# Ampli_ancha.net
KiCad netlist of a schematic drawn in Altium Designer
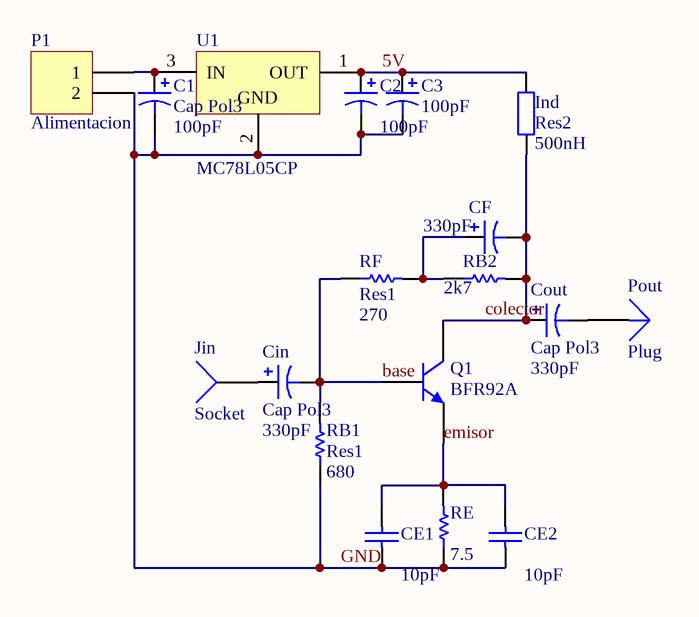
[diagram p0: Ampli_ancha.SchDoc]

(export (version "E")
  (design (tool "Eeschema 10.0.6"))
  (components
    (comp (ref "C1")
      (value "Cap Pol3")
      (footprint "C0805")
      (description "Polarized Capacitor (Surface Mount)")
      (fields (field (name "ALTIUM_VALUE") "100pF") (field (name "PUBLISHER") "Altium Limited"))
      (libsource (lib "Miscellaneous Devices") (part "Cap Pol3"))
    )
    (comp (ref "C2")
      (value "100pF")
      (footprint "C0805")
      (description "Polarized Capacitor (Surface Mount)")
      (fields (field (name "Comment") "Cap Pol3") (field (name "PUBLISHER") "Altium Limited"))
      (libsource (lib "Miscellaneous Devices") (part "Cap Pol3"))
    )
    (comp (ref "C3")
      (value "100pF")
      (footprint "C0805")
      (description "Polarized Capacitor (Surface Mount)")
      (fields (field (name "Comment") "Cap Pol3") (field (name "PUBLISHER") "Altium Limited"))
      (libsource (lib "Miscellaneous Devices") (part "Cap Pol3"))
    )
    (comp (ref "CE1")
      (value "10pF")
      (footprint "1608[0603]")
      (description "Capacitor (Semiconductor SIM Model)")
      (fields (field (name "Comment") "Cap Semi") (field (name "PUBLISHER") "Altium Limited"))
      (libsource (lib "Miscellaneous Devices") (part "Cap Semi"))
    )
    (comp (ref "CE2")
      (value "10pF")
      (footprint "1608[0603]")
      (description "Capacitor (Semiconductor SIM Model)")
      (fields (field (name "Comment") "Cap Semi") (field (name "PUBLISHER") "Altium Limited"))
      (libsource (lib "Miscellaneous Devices") (part "Cap Semi"))
    )
    (comp (ref "CF")
      (value "330pF")
      (footprint "C0805")
      (description "Polarized Capacitor (Surface Mount)")
      (fields (field (name "Comment") "Cap Pol3") (field (name "PUBLISHER") "Altium Limited"))
      (libsource (lib "Miscellaneous Devices") (part "Cap Pol3"))
    )
    (comp (ref "Cin")
      (value "Cap Pol3")
      (footprint "C0805")
      (description "Polarized Capacitor (Surface Mount)")
      (fields (field (name "ALTIUM_VALUE") "330pF") (field (name "PUBLISHER") "Altium Limited"))
      (libsource (lib "Miscellaneous Devices") (part "Cap Pol3"))
    )
    (comp (ref "Cout")
      (value "Cap Pol3")
      (footprint "C0805")
      (description "Polarized Capacitor (Surface Mount)")
      (fields (field (name "ALTIUM_VALUE") "330pF") (field (name "PUBLISHER") "Altium Limited"))
      (libsource (lib "Miscellaneous Devices") (part "Cap Pol3"))
    )
    (comp (ref "Ind")
      (value "Res2")
      (footprint "AXIAL-0.4")
      (description "Resistor")
      (fields (field (name "ALTIUM_VALUE") "500nH") (field (name "PUBLISHER") "Altium Limited"))
      (libsource (lib "Miscellaneous Devices") (part "Res2"))
    )
    (comp (ref "Jin")
      (value "Socket")
      (footprint "PIN1")
      (fields (field (name "PUBLISHER") "Altium Limited"))
      (libsource (lib "Miscellaneous Connectors") (part "Socket"))
    )
    (comp (ref "P1")
      (value "Alimentacion")
      (footprint "HDR1X2")
      (description "Header, 2-Pin")
      (fields (field (name "PUBLISHER") "Altium Limited"))
      (libsource (lib "Miscellaneous Connectors") (part "Header 2"))
    )
    (comp (ref "Pout")
      (value "Plug")
      (footprint "PIN1")
      (fields (field (name "PUBLISHER") "Altium Limited"))
      (libsource (lib "Miscellaneous Connectors") (part "Plug"))
    )
    (comp (ref "Q1")
      (value "BFR92A")
      (footprint "SOT23")
      (description "NPN 5 GHz Wideband Transistor")
      (fields (field (name "PUBLISHER") "Altium Limited"))
      (libsource (lib "Philips Discrete BJT - RF Transistor") (part "BFR92A"))
    )
    (comp (ref "RB1")
      (value "Res1")
      (footprint "AXIAL-0.3")
      (description "Resistor")
      (fields (field (name "ALTIUM_VALUE") "680") (field (name "PUBLISHER") "Altium Limited"))
      (libsource (lib "Miscellaneous Devices") (part "Res1"))
    )
    (comp (ref "RB2")
      (value "2k7")
      (footprint "AXIAL-0.3")
      (description "Resistor")
      (fields (field (name "Comment") "Res1") (field (name "PUBLISHER") "Altium Limited"))
      (libsource (lib "Miscellaneous Devices") (part "Res1"))
    )
    (comp (ref "RE")
      (value "7.5")
      (footprint "2012[0805]")
      (description "Semiconductor Resistor")
      (fields (field (name "Comment") "Res Semi") (field (name "PUBLISHER") "Altium Limited"))
      (libsource (lib "Miscellaneous Devices") (part "Res Semi"))
    )
    (comp (ref "RF")
      (value "Res1")
      (footprint "AXIAL-0.3")
      (description "Resistor")
      (fields (field (name "ALTIUM_VALUE") "270") (field (name "PUBLISHER") "Altium Limited"))
      (libsource (lib "Miscellaneous Devices") (part "Res1"))
    )
    (comp (ref "U1")
      (value "MC78L05CP")
      (footprint "29-04")
      (description "3-Terminal Low-Current Positive Fixed Voltage Regulator")
      (fields (field (name "PUBLISHER") "Altium Limited"))
      (libsource (lib "Motorola Power Mgt Voltage Regulator") (part "MC78L05CP"))
    )
  )
  (nets
    (net (code "1") (name "/5V") (class "Default")
      (node (ref "C2") (pin "1") (pinfunction "1_1") (pintype "passive"))
      (node (ref "C3") (pin "1") (pinfunction "1_1") (pintype "passive"))
      (node (ref "Ind") (pin "2") (pinfunction "2_2") (pintype "passive"))
      (node (ref "U1") (pin "1") (pinfunction "OUT_1") (pintype "power_in"))
    )
    (net (code "2") (name "/GND") (class "Default")
      (node (ref "C1") (pin "2") (pinfunction "2_2") (pintype "passive"))
      (node (ref "C2") (pin "2") (pinfunction "2_2") (pintype "passive"))
      (node (ref "C3") (pin "2") (pinfunction "2_2") (pintype "passive"))
      (node (ref "CE1") (pin "1") (pinfunction "1_1") (pintype "passive"))
      (node (ref "CE2") (pin "1") (pinfunction "1_1") (pintype "passive"))
      (node (ref "P1") (pin "2") (pinfunction "2_2") (pintype "passive"))
      (node (ref "RB1") (pin "1") (pinfunction "1_1") (pintype "passive"))
      (node (ref "RE") (pin "1") (pinfunction "1_1") (pintype "passive"))
      (node (ref "U1") (pin "2") (pinfunction "GND_2") (pintype "power_in"))
    )
    (net (code "3") (name "/base") (class "Default")
      (node (ref "Cin") (pin "2") (pinfunction "2_2") (pintype "passive"))
      (node (ref "Q1") (pin "1") (pinfunction "B_1") (pintype "passive"))
      (node (ref "RB1") (pin "2") (pinfunction "2_2") (pintype "passive"))
      (node (ref "RF") (pin "1") (pinfunction "1_1") (pintype "passive"))
    )
    (net (code "4") (name "/colector") (class "Default")
      (node (ref "CF") (pin "2") (pinfunction "2_2") (pintype "passive"))
      (node (ref "Cout") (pin "1") (pinfunction "1_1") (pintype "passive"))
      (node (ref "Ind") (pin "1") (pinfunction "1_1") (pintype "passive"))
      (node (ref "Q1") (pin "3") (pinfunction "C_3") (pintype "passive"))
      (node (ref "RB2") (pin "2") (pinfunction "2_2") (pintype "passive"))
    )
    (net (code "5") (name "/emisor") (class "Default")
      (node (ref "CE1") (pin "2") (pinfunction "2_2") (pintype "passive"))
      (node (ref "CE2") (pin "2") (pinfunction "2_2") (pintype "passive"))
      (node (ref "Q1") (pin "2") (pinfunction "E_2") (pintype "passive"))
      (node (ref "RE") (pin "2") (pinfunction "2_2") (pintype "passive"))
    )
    (net (code "6") (name "Net-(CF-Pad1)") (class "Default")
      (node (ref "CF") (pin "1") (pinfunction "1_1") (pintype "passive"))
      (node (ref "RB2") (pin "1") (pinfunction "1_1") (pintype "passive"))
      (node (ref "RF") (pin "2") (pinfunction "2_2") (pintype "passive"))
    )
    (net (code "7") (name "Net-(Cin-Pad1)") (class "Default")
      (node (ref "Cin") (pin "1") (pinfunction "1_1") (pintype "passive"))
      (node (ref "Jin") (pin "1") (pinfunction "1_1") (pintype "passive"))
    )
    (net (code "8") (name "Net-(Cout-Pad2)") (class "Default")
      (node (ref "Cout") (pin "2") (pinfunction "2_2") (pintype "passive"))
      (node (ref "Pout") (pin "1") (pinfunction "1_1") (pintype "passive"))
    )
    (net (code "9") (name "Net-(U1-IN)") (class "Default")
      (node (ref "C1") (pin "1") (pinfunction "1_1") (pintype "passive"))
      (node (ref "P1") (pin "1") (pinfunction "1_1") (pintype "passive"))
      (node (ref "U1") (pin "3") (pinfunction "IN_3") (pintype "power_in"))
    )
  )
)
